# Vibrator.net
KiCad netlist of a schematic drawn in Altium Designer
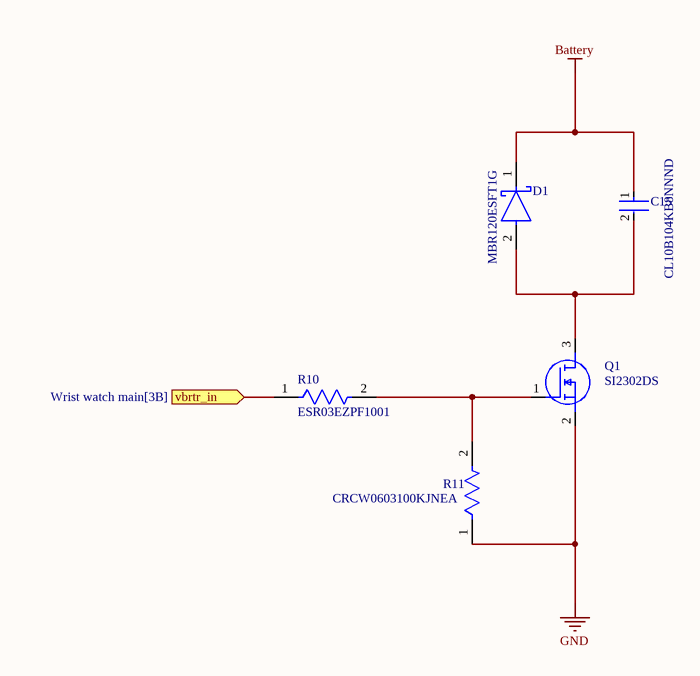
[diagram p0: Vibrator.SchDoc]

(export (version "E")
  (design (tool "Eeschema 10.0.6"))
  (components
    (comp (ref "C15")
      (value "CL10B104KB8NNND")
      (footprint "FP-CL10-IPC_A")
      (description "Cap Ceramic 100nF 50V X7R ±10% Pad SMD 0603 +125°C T/R")
      (fields (field (name "VOLTAGE") "50V") (field (name "TOLERANCE") "10%"))
      (libsource (lib "Altium Content Vault") (part "b4654b650e69147ec39a6b967a45e02"))
    )
    (comp (ref "D1")
      (value "MBR120ESFT1G")
      (footprint "On_Semiconductor_498_MFG")
      (libsource (lib "Altium Content Vault") (part "MBR120ESFT1G"))
    )
    (comp (ref "Q1")
      (value "SI2302DS")
      (footprint "SamacSys:SOT95P230X110-3N")
      (description "MOSFET (N-Channel)")
      (libsource (lib "*") (part "SI2302DS"))
    )
    (comp (ref "R10")
      (value "ESR03EZPF1001")
      (footprint "FP-ESR03-IPC_A")
      (description "1kΩ ±1% 0.25W 0603 Anti-Surge Chip Resistor AEC-Q200")
      (fields (field (name "TOLERANCE") "1%"))
      (libsource (lib "Altium Content Vault") (part "1029c3af85768c4190bb7ad29bc67b5"))
    )
    (comp (ref "R11")
      (value "CRCW0603100KJNEA")
      (footprint "FP-CRCW0603-e3-IPC_C")
      (description "RES Thick Film, 100kΩ, 5%, 0.1W, 200ppm/°C, 0603")
      (fields (field (name "TOLERANCE") "5%"))
      (libsource (lib "Altium Content Vault") (part "1029c3af85768c4190bb7ad29bc67b5"))
    )
  )
  (nets
    (net (code "1") (name "/vbrtr_in") (class "Default")
      (node (ref "R10") (pin "1") (pinfunction "1_1") (pintype "passive"))
    )
    (net (code "2") (name "Battery") (class "Default")
      (node (ref "C15") (pin "1") (pinfunction "1_1") (pintype "passive"))
      (node (ref "D1") (pin "1") (pinfunction "C_1") (pintype "passive"))
    )
    (net (code "3") (name "GND") (class "Default")
      (node (ref "Q1") (pin "2") (pinfunction "S_2") (pintype "passive"))
      (node (ref "R11") (pin "1") (pinfunction "1_1") (pintype "passive"))
    )
    (net (code "4") (name "Net-(D1-A)") (class "Default")
      (node (ref "C15") (pin "2") (pinfunction "2_2") (pintype "passive"))
      (node (ref "D1") (pin "2") (pinfunction "A_2") (pintype "passive"))
      (node (ref "Q1") (pin "3") (pinfunction "D_3") (pintype "passive"))
    )
    (net (code "5") (name "Net-(Q1-G)") (class "Default")
      (node (ref "Q1") (pin "1") (pinfunction "G_1") (pintype "passive"))
      (node (ref "R10") (pin "2") (pinfunction "2_2") (pintype "passive"))
      (node (ref "R11") (pin "2") (pinfunction "2_2") (pintype "passive"))
    )
  )
)
